# gravador.net
KiCad netlist of a schematic drawn in Altium Designer
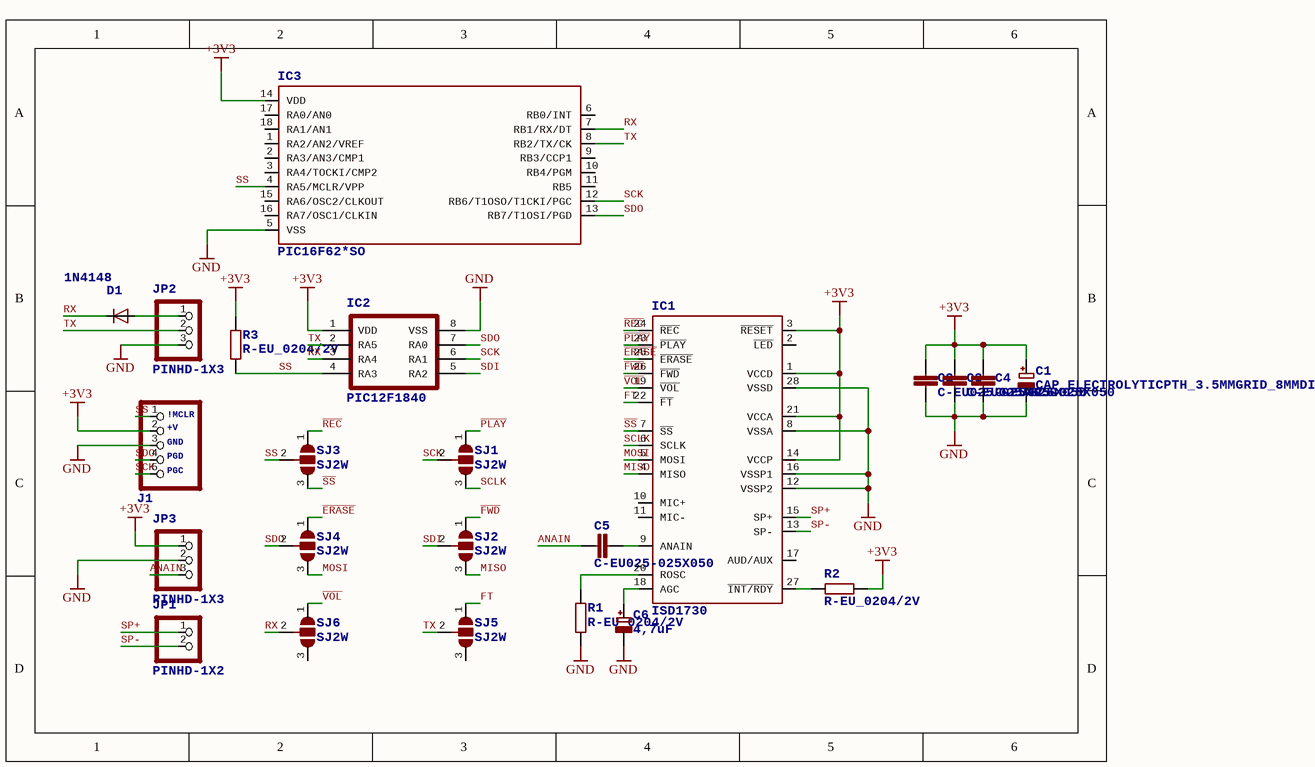
[diagram p0: gravador.SchDoc]

(export (version "E")
  (design (tool "Eeschema 10.0.6"))
  (components
    (comp (ref "C1")
      (value "CAP_ELECTROLYTICPTH_3.5MMGRID_8MMDIA")
      (footprint "CELEC_3.5MM_8MM")
      (libsource (lib "junior") (part "CAP_ELECTROLYTICPTH_3.5MMGRID_8MMDIA"))
    )
    (comp (ref "C2")
      (value "C-EU025-025X050")
      (footprint "C025-025X050")
      (description "CAPACITOR, European symbol")
      (libsource (lib "") (part "C-EU025-025X050_1"))
    )
    (comp (ref "C3")
      (value "C-EU025-025X050")
      (footprint "C025-025X050")
      (description "CAPACITOR, European symbol")
      (libsource (lib "") (part "C-EU025-025X050_1"))
    )
    (comp (ref "C4")
      (value "C-EU025-025X050")
      (footprint "C025-025X050")
      (description "CAPACITOR, European symbol")
      (libsource (lib "") (part "C-EU025-025X050_1"))
    )
    (comp (ref "C5")
      (value "C-EU025-025X050")
      (footprint "C025-025X050")
      (description "CAPACITOR, European symbol")
      (libsource (lib "rcl") (part "C-EU025-025X050"))
    )
    (comp (ref "C6")
      (value "4,7uF")
      (footprint "CELEC_3.5MM_8MM")
      (libsource (lib "junior") (part "CAP_ELECTROLYTICPTH_3.5MMGRID_8MMDIA"))
    )
    (comp (ref "D1")
      (value "1N4148")
      (footprint "DO35-7")
      (description "DIODE   high speed (Philips)")
      (libsource (lib "diode") (part "1N4148DO35-7"))
    )
    (comp (ref "IC1")
      (value "ISD1730")
      (footprint "SOP28_300MIL")
      (libsource (lib "junior") (part "ISD1730"))
    )
    (comp (ref "IC2")
      (value "PIC12F1840")
      (footprint "DFN6_3X3")
      (libsource (lib "dp_devices") (part "IC_UC_PIC12F1822DFN6_3X3"))
    )
    (comp (ref "IC3")
      (value "PIC16F62*SO")
      (footprint "SO-18W")
      (fields (field (name "MF") "MICROCHIP") (field (name "MPN") "PIC16F627-04I/SO"))
      (libsource (lib "microchip") (part "PIC16F62*SO"))
    )
    (comp (ref "J1")
      (value "CON_HEADER_PRG_PIC_ICSP0.1INCH_B")
      (footprint "HEADER_PRG_1X05_ICSP_B")
      (description "5-pin PIC In Circuit Serial Programming header")
      (fields
        (field (name "!MCLR") "!MCLR")
        (field (name "+V") "+V")
        (field (name "GND") "GND")
        (field (name "PGD") "PGD")
        (field (name "PGC") "PGC")
      )
      (libsource (lib "dp_devices") (part "CON_HEADER_PRG_PIC_ICSP0.1INCH_B"))
    )
    (comp (ref "JP1")
      (value "PINHD-1X2")
      (footprint "1X02")
      (description "PIN HEADER")
      (libsource (lib "pinhead") (part "PINHD-1X2"))
    )
    (comp (ref "JP2")
      (value "PINHD-1X3")
      (footprint "1X03")
      (description "PIN HEADER")
      (libsource (lib "pinhead") (part "PINHD-1X3"))
    )
    (comp (ref "JP3")
      (value "PINHD-1X3")
      (footprint "1X03")
      (description "PIN HEADER")
      (libsource (lib "pinhead") (part "PINHD-1X3"))
    )
    (comp (ref "R1")
      (value "R-EU_0204/2V")
      (footprint "0204V")
      (description "RESISTOR, European symbol")
      (libsource (lib "rcl") (part "R-EU_0204/2V"))
    )
    (comp (ref "R2")
      (value "R-EU_0204/2V")
      (footprint "0204V")
      (description "RESISTOR, European symbol")
      (libsource (lib "rcl") (part "R-EU_0204/2V"))
    )
    (comp (ref "R3")
      (value "R-EU_0204/2V")
      (footprint "0204V")
      (description "RESISTOR, European symbol")
      (libsource (lib "rcl") (part "R-EU_0204/2V"))
    )
    (comp (ref "SJ1")
      (value "SJ2W")
      (footprint "SJ_2")
      (description "SMD solder JUMPER")
      (libsource (lib "jumper") (part "SJ2W"))
    )
    (comp (ref "SJ2")
      (value "SJ2W")
      (footprint "SJ_2")
      (description "SMD solder JUMPER")
      (libsource (lib "jumper") (part "SJ2W"))
    )
    (comp (ref "SJ3")
      (value "SJ2W")
      (footprint "SJ_2")
      (description "SMD solder JUMPER")
      (libsource (lib "jumper") (part "SJ2W"))
    )
    (comp (ref "SJ4")
      (value "SJ2W")
      (footprint "SJ_2")
      (description "SMD solder JUMPER")
      (libsource (lib "jumper") (part "SJ2W"))
    )
    (comp (ref "SJ5")
      (value "SJ2W")
      (footprint "SJ_2")
      (description "SMD solder JUMPER")
      (libsource (lib "jumper") (part "SJ2W"))
    )
    (comp (ref "SJ6")
      (value "SJ2W")
      (footprint "SJ_2")
      (description "SMD solder JUMPER")
      (libsource (lib "jumper") (part "SJ2W"))
    )
  )
  (nets
    (net (code "1") (name "+3V3") (class "Default")
      (node (ref "C1") (pin "+") (pinfunction "+_+") (pintype "passive"))
      (node (ref "C2") (pin "1") (pinfunction "1_1") (pintype "passive"))
      (node (ref "C3") (pin "1") (pinfunction "1_1") (pintype "passive"))
      (node (ref "C4") (pin "1") (pinfunction "1_1") (pintype "passive"))
      (node (ref "IC1") (pin "1") (pinfunction "VCCD_1") (pintype "power_in"))
      (node (ref "IC1") (pin "14") (pinfunction "VCCP_14") (pintype "power_in"))
      (node (ref "IC1") (pin "21") (pinfunction "VCCA_21") (pintype "power_in"))
      (node (ref "IC1") (pin "3") (pinfunction "~{RESET}_3") (pintype "passive"))
      (node (ref "IC2") (pin "1") (pinfunction "VDD_1") (pintype "power_in"))
      (node (ref "IC3") (pin "14") (pinfunction "VDD_14") (pintype "power_in"))
      (node (ref "J1") (pin "2") (pinfunction "+V_2") (pintype "passive"))
      (node (ref "JP3") (pin "1") (pinfunction "1_1") (pintype "passive"))
      (node (ref "R2") (pin "1") (pinfunction "1_1") (pintype "passive"))
      (node (ref "R3") (pin "1") (pinfunction "1_1") (pintype "passive"))
    )
    (net (code "2") (name "/ANAIN") (class "Default")
      (node (ref "C5") (pin "1") (pinfunction "1_1") (pintype "passive"))
      (node (ref "JP3") (pin "3") (pinfunction "3_3") (pintype "passive"))
    )
    (net (code "3") (name "/FT") (class "Default")
      (node (ref "IC1") (pin "22") (pinfunction "~{FT}_22") (pintype "passive"))
      (node (ref "SJ5") (pin "1") (pinfunction "1_1") (pintype "passive"))
    )
    (net (code "4") (name "/MISO") (class "Default")
      (node (ref "IC1") (pin "4") (pinfunction "MISO_4") (pintype "passive"))
      (node (ref "SJ2") (pin "3") (pinfunction "3_3") (pintype "passive"))
    )
    (net (code "5") (name "/MOSI") (class "Default")
      (node (ref "IC1") (pin "5") (pinfunction "MOSI_5") (pintype "passive"))
      (node (ref "SJ4") (pin "3") (pinfunction "3_3") (pintype "passive"))
    )
    (net (code "6") (name "/RX") (class "Default")
      (node (ref "D1") (pin "C") (pinfunction "C_C") (pintype "passive"))
      (node (ref "IC2") (pin "3") (pinfunction "RA4_3") (pintype "passive"))
      (node (ref "IC3") (pin "7") (pinfunction "RB1/RX/DT_7") (pintype "passive"))
      (node (ref "SJ6") (pin "2") (pinfunction "2_2") (pintype "passive"))
    )
    (net (code "7") (name "/SCK") (class "Default")
      (node (ref "IC2") (pin "6") (pinfunction "RA1_6") (pintype "passive"))
      (node (ref "IC3") (pin "12") (pinfunction "RB6/T1OSO/T1CKI/PGC_12") (pintype "passive"))
      (node (ref "J1") (pin "5") (pinfunction "PGC_5") (pintype "passive"))
      (node (ref "SJ1") (pin "2") (pinfunction "2_2") (pintype "passive"))
    )
    (net (code "8") (name "/SCLK") (class "Default")
      (node (ref "IC1") (pin "6") (pinfunction "SCLK_6") (pintype "passive"))
      (node (ref "SJ1") (pin "3") (pinfunction "3_3") (pintype "passive"))
    )
    (net (code "9") (name "/SDI") (class "Default")
      (node (ref "IC2") (pin "5") (pinfunction "RA2_5") (pintype "passive"))
      (node (ref "SJ2") (pin "2") (pinfunction "2_2") (pintype "passive"))
    )
    (net (code "10") (name "/SDO") (class "Default")
      (node (ref "IC2") (pin "7") (pinfunction "RA0_7") (pintype "passive"))
      (node (ref "IC3") (pin "13") (pinfunction "RB7/T1OSI/PGD_13") (pintype "passive"))
      (node (ref "J1") (pin "4") (pinfunction "PGD_4") (pintype "passive"))
      (node (ref "SJ4") (pin "2") (pinfunction "2_2") (pintype "passive"))
    )
    (net (code "11") (name "/SP+") (class "Default")
      (node (ref "IC1") (pin "15") (pinfunction "SP+_15") (pintype "passive"))
      (node (ref "JP1") (pin "1") (pinfunction "1_1") (pintype "passive"))
    )
    (net (code "12") (name "/SP-") (class "Default")
      (node (ref "IC1") (pin "13") (pinfunction "SP-_13") (pintype "passive"))
      (node (ref "JP1") (pin "2") (pinfunction "2_2") (pintype "passive"))
    )
    (net (code "13") (name "/SS") (class "Default")
      (node (ref "IC2") (pin "4") (pinfunction "RA3_4") (pintype "passive"))
      (node (ref "IC3") (pin "4") (pinfunction "RA5/MCLR/VPP_4") (pintype "passive"))
      (node (ref "J1") (pin "1") (pinfunction "/MCLR_1") (pintype "passive"))
      (node (ref "R3") (pin "2") (pinfunction "2_2") (pintype "passive"))
      (node (ref "SJ3") (pin "2") (pinfunction "2_2") (pintype "passive"))
    )
    (net (code "14") (name "/TX") (class "Default")
      (node (ref "IC2") (pin "2") (pinfunction "RA5_2") (pintype "passive"))
      (node (ref "IC3") (pin "8") (pinfunction "RB2/TX/CK_8") (pintype "passive"))
      (node (ref "JP2") (pin "2") (pinfunction "2_2") (pintype "passive"))
      (node (ref "SJ5") (pin "2") (pinfunction "2_2") (pintype "passive"))
    )
    (net (code "15") (name "/~{ERASE}") (class "Default")
      (node (ref "IC1") (pin "25") (pinfunction "~{ERASE}_25") (pintype "passive"))
      (node (ref "SJ4") (pin "1") (pinfunction "1_1") (pintype "passive"))
    )
    (net (code "16") (name "/~{FWD}") (class "Default")
      (node (ref "IC1") (pin "26") (pinfunction "~{FWD}_26") (pintype "passive"))
      (node (ref "SJ2") (pin "1") (pinfunction "1_1") (pintype "passive"))
    )
    (net (code "17") (name "/~{PLAY}") (class "Default")
      (node (ref "IC1") (pin "23") (pinfunction "~{PLAY}_23") (pintype "passive"))
      (node (ref "SJ1") (pin "1") (pinfunction "1_1") (pintype "passive"))
    )
    (net (code "18") (name "/~{REC}") (class "Default")
      (node (ref "IC1") (pin "24") (pinfunction "~{REC}_24") (pintype "passive"))
      (node (ref "SJ3") (pin "1") (pinfunction "1_1") (pintype "passive"))
    )
    (net (code "19") (name "/~{SS}") (class "Default")
      (node (ref "IC1") (pin "7") (pinfunction "~{SS}_7") (pintype "passive"))
      (node (ref "SJ3") (pin "3") (pinfunction "3_3") (pintype "passive"))
    )
    (net (code "20") (name "/~{VOL}") (class "Default")
      (node (ref "IC1") (pin "19") (pinfunction "~{VOL}_19") (pintype "passive"))
      (node (ref "SJ6") (pin "1") (pinfunction "1_1") (pintype "passive"))
    )
    (net (code "21") (name "GND") (class "Default")
      (node (ref "C1") (pin "-") (pinfunction "-_-") (pintype "passive"))
      (node (ref "C2") (pin "2") (pinfunction "2_2") (pintype "passive"))
      (node (ref "C3") (pin "2") (pinfunction "2_2") (pintype "passive"))
      (node (ref "C4") (pin "2") (pinfunction "2_2") (pintype "passive"))
      (node (ref "C6") (pin "-") (pinfunction "-_-") (pintype "passive"))
      (node (ref "IC1") (pin "12") (pinfunction "VSSP2_12") (pintype "power_in"))
      (node (ref "IC1") (pin "16") (pinfunction "VSSP1_16") (pintype "power_in"))
      (node (ref "IC1") (pin "28") (pinfunction "VSSD_28") (pintype "power_in"))
      (node (ref "IC1") (pin "8") (pinfunction "VSSA_8") (pintype "power_in"))
      (node (ref "IC2") (pin "8") (pinfunction "VSS_8") (pintype "power_in"))
      (node (ref "IC3") (pin "5") (pinfunction "VSS_5") (pintype "power_in"))
      (node (ref "J1") (pin "3") (pinfunction "GND_3") (pintype "passive"))
      (node (ref "JP2") (pin "3") (pinfunction "3_3") (pintype "passive"))
      (node (ref "JP3") (pin "2") (pinfunction "2_2") (pintype "passive"))
      (node (ref "R1") (pin "1") (pinfunction "1_1") (pintype "passive"))
    )
    (net (code "22") (name "Net-(D1-PadA)") (class "Default")
      (node (ref "D1") (pin "A") (pinfunction "A_A") (pintype "passive"))
      (node (ref "JP2") (pin "1") (pinfunction "1_1") (pintype "passive"))
    )
    (net (code "23") (name "Net-(IC1-AGC)") (class "Default")
      (node (ref "C6") (pin "+") (pinfunction "+_+") (pintype "passive"))
      (node (ref "IC1") (pin "18") (pinfunction "AGC_18") (pintype "passive"))
    )
    (net (code "24") (name "Net-(IC1-ANAIN)") (class "Default")
      (node (ref "C5") (pin "2") (pinfunction "2_2") (pintype "passive"))
      (node (ref "IC1") (pin "9") (pinfunction "ANAIN_9") (pintype "passive"))
    )
    (net (code "25") (name "Net-(IC1-ROSC)") (class "Default")
      (node (ref "IC1") (pin "20") (pinfunction "ROSC_20") (pintype "passive"))
      (node (ref "R1") (pin "2") (pinfunction "2_2") (pintype "passive"))
    )
    (net (code "26") (name "Net-(IC1-~{INT{slash}RDY})") (class "Default")
      (node (ref "IC1") (pin "27") (pinfunction "~{INT/RDY}_27") (pintype "passive"))
      (node (ref "R2") (pin "2") (pinfunction "2_2") (pintype "passive"))
    )
    (net (code "27") (name "unconnected-(IC1-AUD{slash}AUX-Pad17)") (class "Default")
      (node (ref "IC1") (pin "17") (pinfunction "AUD/AUX_17") (pintype "passive"))
    )
    (net (code "28") (name "unconnected-(IC1-MIC+-Pad10)") (class "Default")
      (node (ref "IC1") (pin "10") (pinfunction "MIC+_10") (pintype "passive"))
    )
    (net (code "29") (name "unconnected-(IC1-MIC--Pad11)") (class "Default")
      (node (ref "IC1") (pin "11") (pinfunction "MIC-_11") (pintype "passive"))
    )
    (net (code "30") (name "unconnected-(IC1-~{LED}-Pad2)") (class "Default")
      (node (ref "IC1") (pin "2") (pinfunction "~{LED}_2") (pintype "passive"))
    )
    (net (code "31") (name "unconnected-(IC3-RA0{slash}AN0-Pad17)") (class "Default")
      (node (ref "IC3") (pin "17") (pinfunction "RA0/AN0_17") (pintype "passive"))
    )
    (net (code "32") (name "unconnected-(IC3-RA1{slash}AN1-Pad18)") (class "Default")
      (node (ref "IC3") (pin "18") (pinfunction "RA1/AN1_18") (pintype "passive"))
    )
    (net (code "33") (name "unconnected-(IC3-RA2{slash}AN2{slash}VREF-Pad1)") (class "Default")
      (node (ref "IC3") (pin "1") (pinfunction "RA2/AN2/VREF_1") (pintype "passive"))
    )
    (net (code "34") (name "unconnected-(IC3-RA3{slash}AN3{slash}CMP1-Pad2)") (class "Default")
      (node (ref "IC3") (pin "2") (pinfunction "RA3/AN3/CMP1_2") (pintype "passive"))
    )
    (net (code "35") (name "unconnected-(IC3-RA4{slash}TOCKI{slash}CMP2-Pad3)") (class "Default")
      (node (ref "IC3") (pin "3") (pinfunction "RA4/TOCKI/CMP2_3") (pintype "passive"))
    )
    (net (code "36") (name "unconnected-(IC3-RA6{slash}OSC2{slash}CLKOUT-Pad15)") (class "Default")
      (node (ref "IC3") (pin "15") (pinfunction "RA6/OSC2/CLKOUT_15") (pintype "passive"))
    )
    (net (code "37") (name "unconnected-(IC3-RA7{slash}OSC1{slash}CLKIN-Pad16)") (class "Default")
      (node (ref "IC3") (pin "16") (pinfunction "RA7/OSC1/CLKIN_16") (pintype "passive"))
    )
    (net (code "38") (name "unconnected-(IC3-RB0{slash}INT-Pad6)") (class "Default")
      (node (ref "IC3") (pin "6") (pinfunction "RB0/INT_6") (pintype "passive"))
    )
    (net (code "39") (name "unconnected-(IC3-RB3{slash}CCP1-Pad9)") (class "Default")
      (node (ref "IC3") (pin "9") (pinfunction "RB3/CCP1_9") (pintype "passive"))
    )
    (net (code "40") (name "unconnected-(IC3-RB4{slash}PGM-Pad10)") (class "Default")
      (node (ref "IC3") (pin "10") (pinfunction "RB4/PGM_10") (pintype "passive"))
    )
    (net (code "41") (name "unconnected-(IC3-RB5-Pad11)") (class "Default")
      (node (ref "IC3") (pin "11") (pinfunction "RB5_11") (pintype "passive"))
    )
    (net (code "42") (name "unconnected-(SJ5-Pad3)") (class "Default")
      (node (ref "SJ5") (pin "3") (pinfunction "3_3") (pintype "passive"))
    )
    (net (code "43") (name "unconnected-(SJ6-Pad3)") (class "Default")
      (node (ref "SJ6") (pin "3") (pinfunction "3_3") (pintype "passive"))
    )
  )
)
